# GlacTracker_PSU.net
KiCad netlist of a schematic drawn in EAGLE
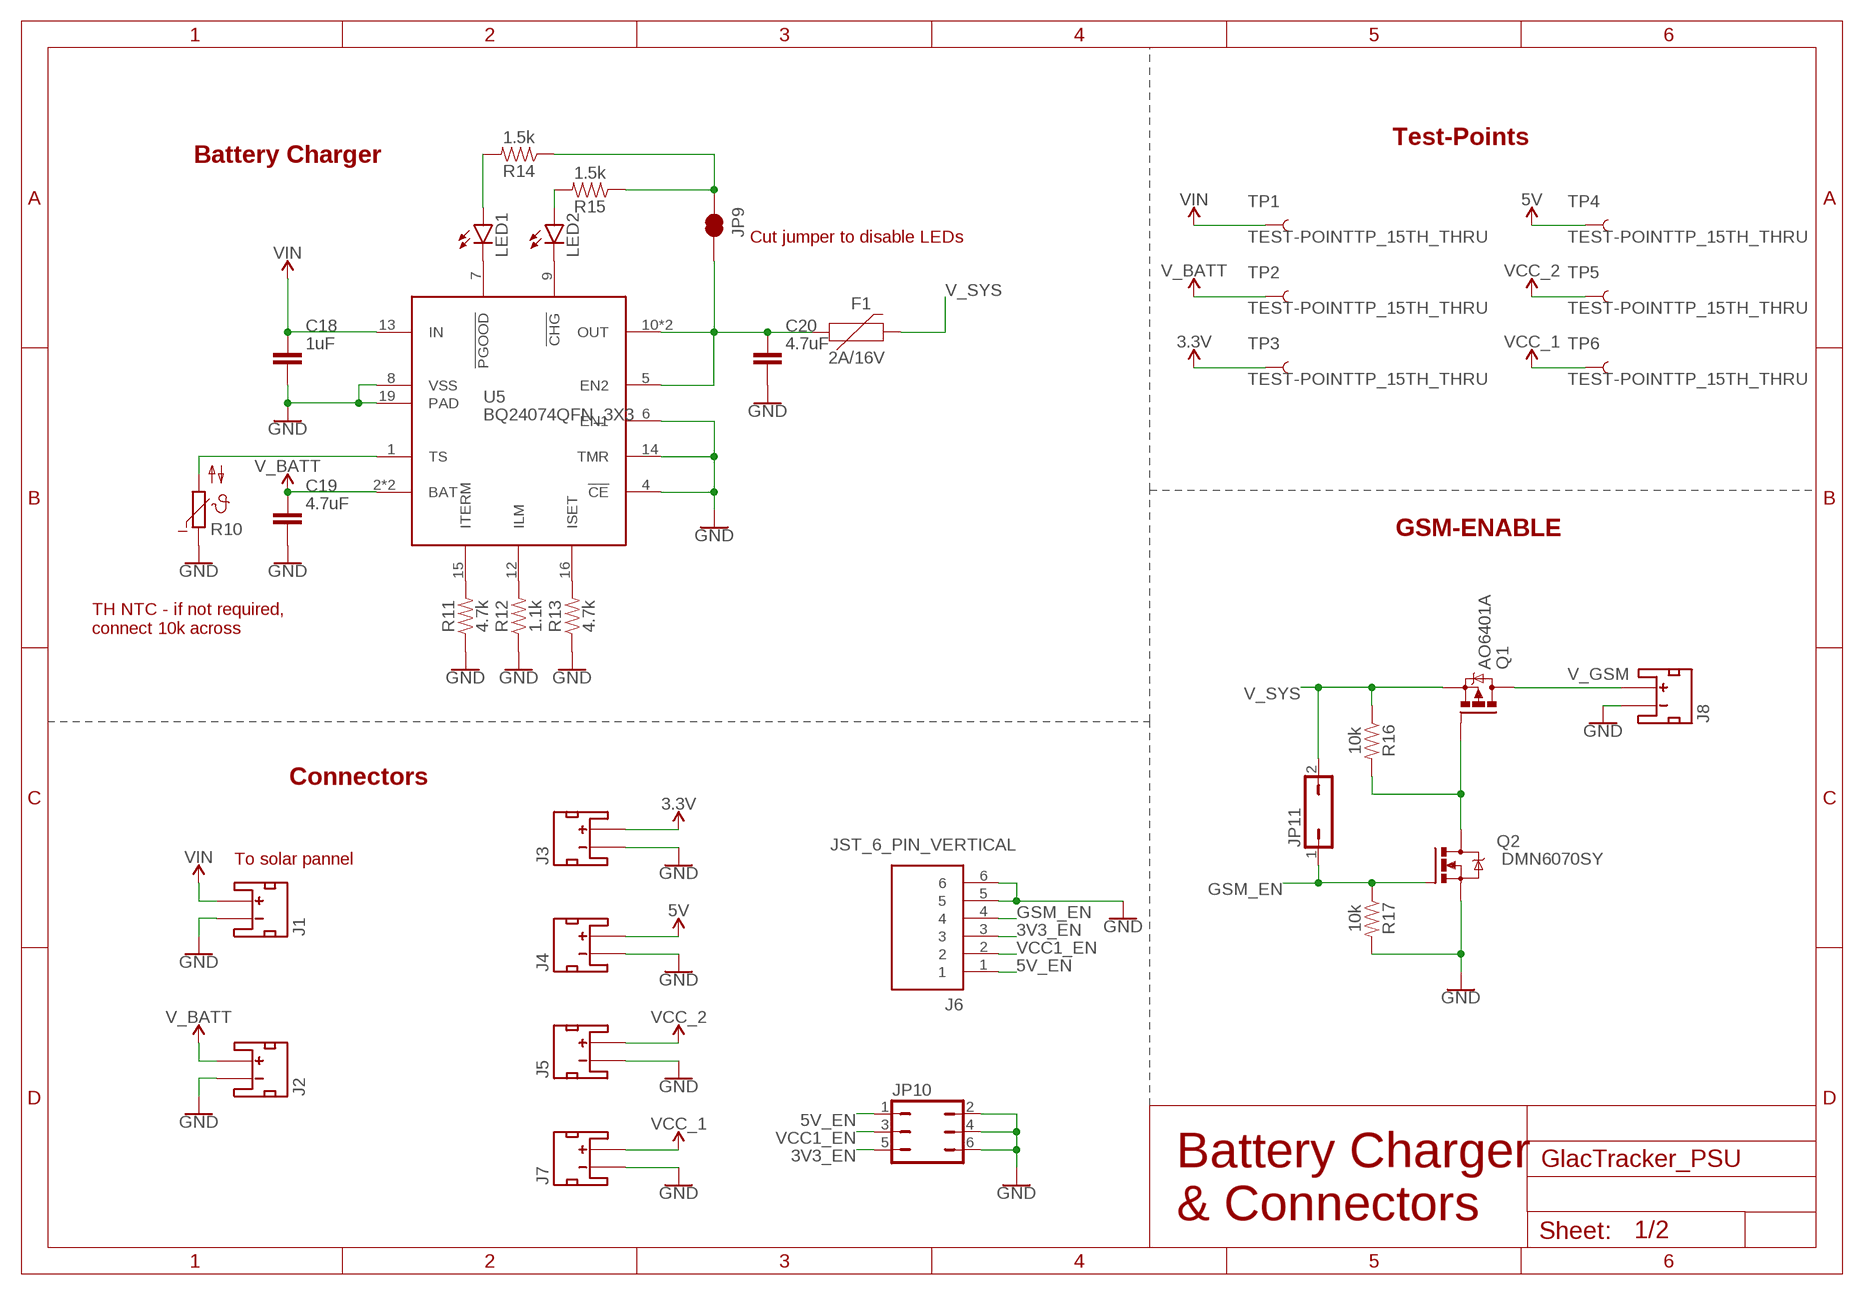
[diagram p0: schematic, sheet 1]
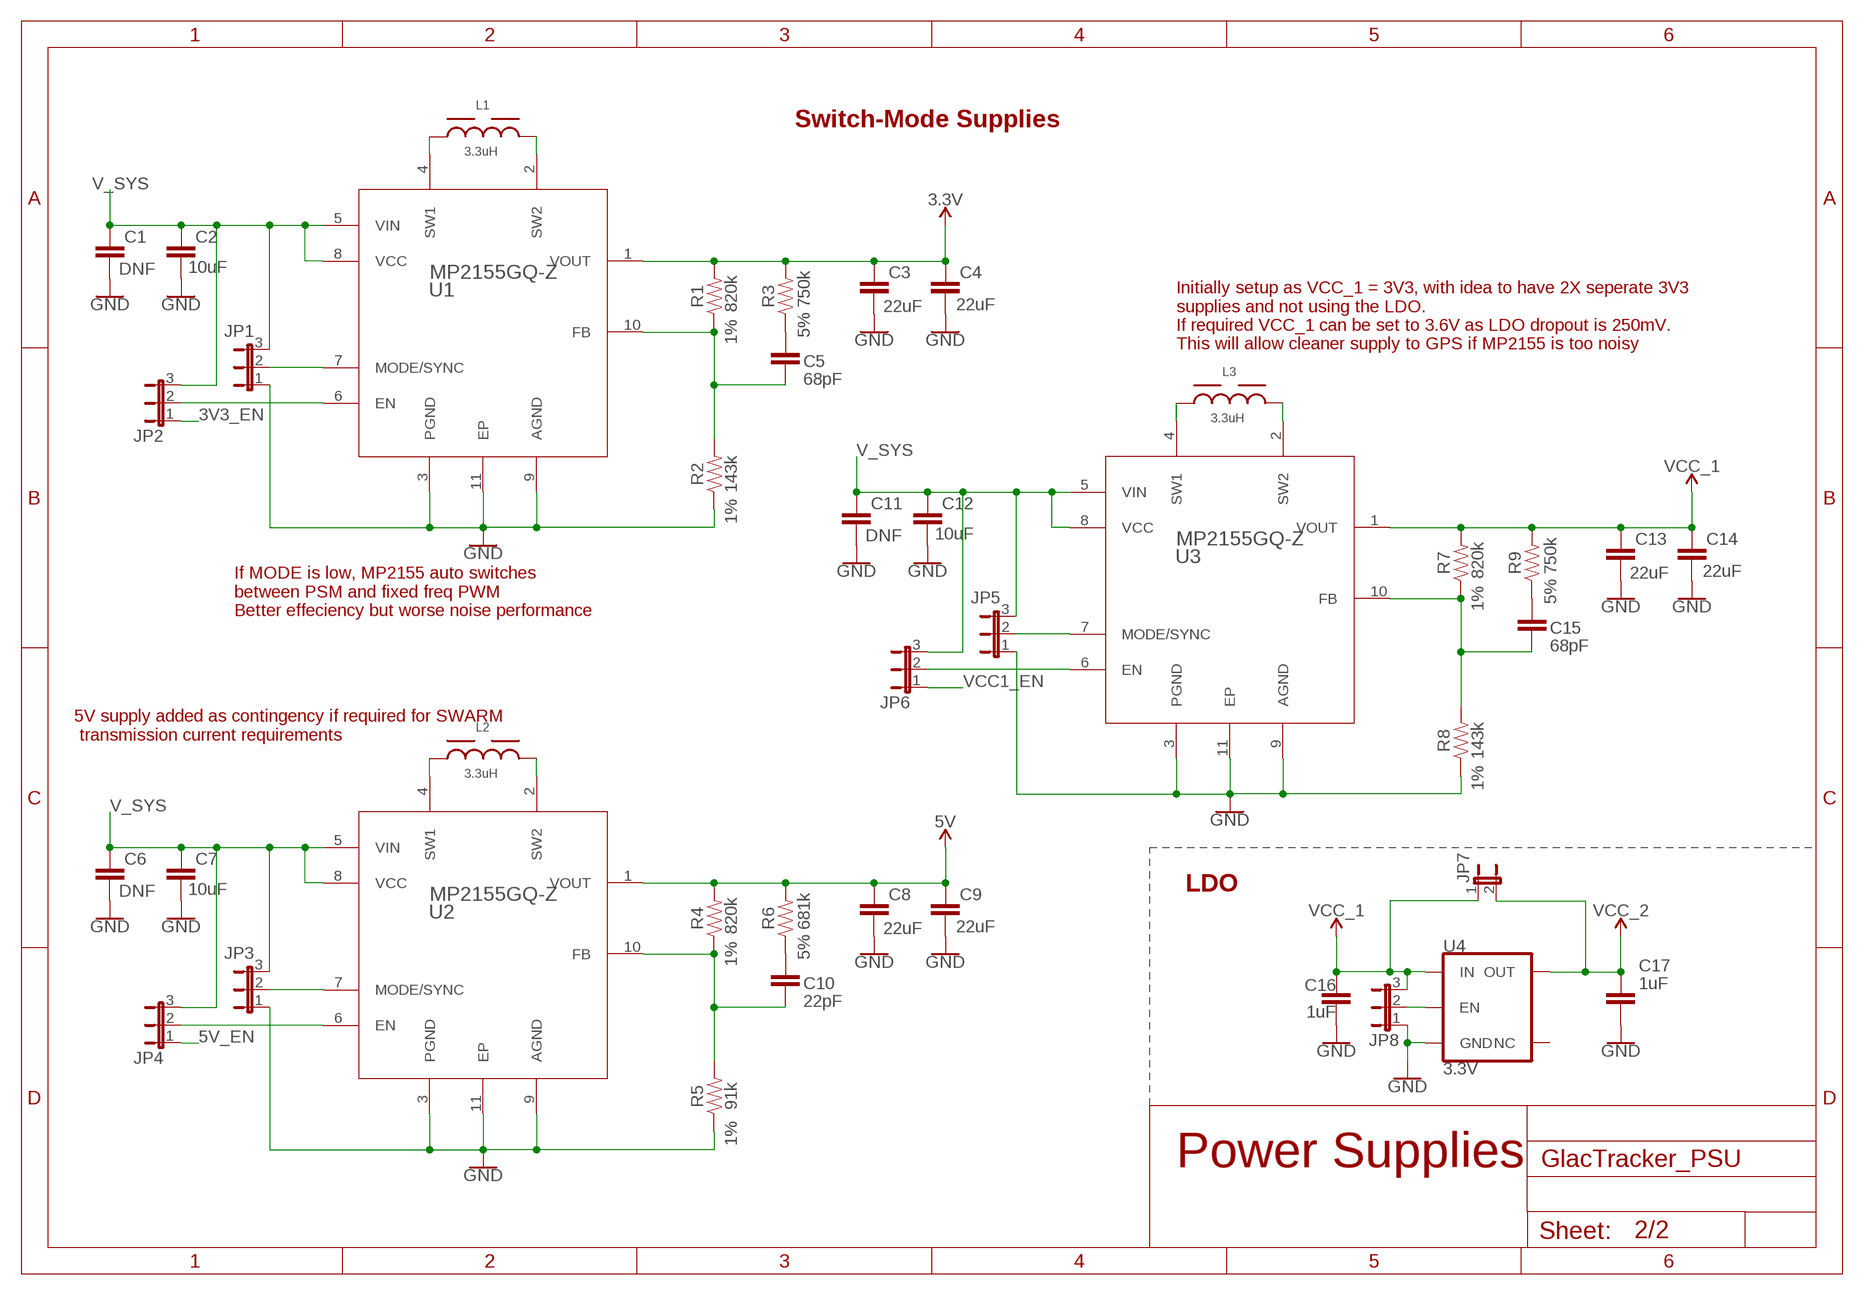
[diagram p1: schematic, sheet 2]

(export (version "E")
  (design (tool "Eeschema 10.0.6"))
  (components
    (comp (ref "C1")
      (value "DNF")
      (footprint "eagle-import:CAPC2012X110")
      (libsource (lib "eagle-import") (part "CCHIP-0805(2012-METRIC)_"))
    )
    (comp (ref "C2")
      (value "10uF")
      (footprint "eagle-import:CAPC2012X110")
      (fields (field (name "TYPE") "X7R") (field (name "VOLTAGE_RATING") "6.3V"))
      (libsource (lib "eagle-import") (part "CCHIP-0805(2012-METRIC)_"))
    )
    (comp (ref "C3")
      (value "22uF")
      (footprint "eagle-import:CAPC2012X110")
      (fields (field (name "TYPE") "X5R") (field (name "VOLTAGE_RATING") "10V"))
      (libsource (lib "eagle-import") (part "CCHIP-0805(2012-METRIC)_"))
    )
    (comp (ref "C4")
      (value "22uF")
      (footprint "eagle-import:CAPC2012X110")
      (fields (field (name "TYPE") "X5R") (field (name "VOLTAGE_RATING") "10V"))
      (libsource (lib "eagle-import") (part "CCHIP-0805(2012-METRIC)_"))
    )
    (comp (ref "C5")
      (value "68pF")
      (footprint "eagle-import:CAPC1608X85")
      (fields (field (name "TYPE") "X7R") (field (name "VOLTAGE_RATING") "50V"))
      (libsource (lib "eagle-import") (part "CCHIP-0603(1608-METRIC)_"))
    )
    (comp (ref "C6")
      (value "DNF")
      (footprint "eagle-import:CAPC2012X110")
      (libsource (lib "eagle-import") (part "CCHIP-0805(2012-METRIC)_"))
    )
    (comp (ref "C7")
      (value "10uF")
      (footprint "eagle-import:CAPC2012X110")
      (fields (field (name "TYPE") "X7R") (field (name "VOLTAGE_RATING") "6.3V"))
      (libsource (lib "eagle-import") (part "CCHIP-0805(2012-METRIC)_"))
    )
    (comp (ref "C8")
      (value "22uF")
      (footprint "eagle-import:CAPC2012X110")
      (fields (field (name "TYPE") "X5R") (field (name "VOLTAGE_RATING") "10V"))
      (libsource (lib "eagle-import") (part "CCHIP-0805(2012-METRIC)_"))
    )
    (comp (ref "C9")
      (value "22uF")
      (footprint "eagle-import:CAPC2012X110")
      (fields (field (name "TYPE") "X5R") (field (name "VOLTAGE_RATING") "10V"))
      (libsource (lib "eagle-import") (part "CCHIP-0805(2012-METRIC)_"))
    )
    (comp (ref "C10")
      (value "22pF")
      (footprint "eagle-import:CAPC1608X85")
      (fields (field (name "TYPE") "X7R") (field (name "VOLTAGE_RATING") "50V"))
      (libsource (lib "eagle-import") (part "CCHIP-0603(1608-METRIC)_"))
    )
    (comp (ref "C11")
      (value "DNF")
      (footprint "eagle-import:CAPC2012X110")
      (libsource (lib "eagle-import") (part "CCHIP-0805(2012-METRIC)_"))
    )
    (comp (ref "C12")
      (value "10uF")
      (footprint "eagle-import:CAPC2012X110")
      (fields (field (name "TYPE") "X7R") (field (name "VOLTAGE_RATING") "6.3V"))
      (libsource (lib "eagle-import") (part "CCHIP-0805(2012-METRIC)_"))
    )
    (comp (ref "C13")
      (value "22uF")
      (footprint "eagle-import:CAPC2012X110")
      (fields (field (name "TYPE") "X5R") (field (name "VOLTAGE_RATING") "10V"))
      (libsource (lib "eagle-import") (part "CCHIP-0805(2012-METRIC)_"))
    )
    (comp (ref "C14")
      (value "22uF")
      (footprint "eagle-import:CAPC2012X110")
      (fields (field (name "TYPE") "X5R") (field (name "VOLTAGE_RATING") "10V"))
      (libsource (lib "eagle-import") (part "CCHIP-0805(2012-METRIC)_"))
    )
    (comp (ref "C15")
      (value "68pF")
      (footprint "eagle-import:CAPC1608X85")
      (fields (field (name "TYPE") "X7R") (field (name "VOLTAGE_RATING") "50V"))
      (libsource (lib "eagle-import") (part "CCHIP-0603(1608-METRIC)_"))
    )
    (comp (ref "C16")
      (value "1uF")
      (footprint "eagle-import:CAPC2012X110")
      (libsource (lib "eagle-import") (part "CCHIP-0805(2012-METRIC)_"))
    )
    (comp (ref "C17")
      (value "1uF")
      (footprint "eagle-import:CAPC2012X110")
      (libsource (lib "eagle-import") (part "CCHIP-0805(2012-METRIC)_"))
    )
    (comp (ref "JP1")
      (value "JP2E")
      (footprint "eagle-import:JP2")
      (libsource (lib "eagle-import") (part "JP2E"))
    )
    (comp (ref "JP2")
      (value "JP2E")
      (footprint "eagle-import:JP2")
      (libsource (lib "eagle-import") (part "JP2E"))
    )
    (comp (ref "JP3")
      (value "JP2E")
      (footprint "eagle-import:JP2")
      (libsource (lib "eagle-import") (part "JP2E"))
    )
    (comp (ref "JP4")
      (value "JP2E")
      (footprint "eagle-import:JP2")
      (libsource (lib "eagle-import") (part "JP2E"))
    )
    (comp (ref "JP5")
      (value "JP2E")
      (footprint "eagle-import:JP2")
      (libsource (lib "eagle-import") (part "JP2E"))
    )
    (comp (ref "JP6")
      (value "JP2E")
      (footprint "eagle-import:JP2")
      (libsource (lib "eagle-import") (part "JP2E"))
    )
    (comp (ref "JP7")
      (value "JP1E")
      (footprint "eagle-import:JP1")
      (libsource (lib "eagle-import") (part "JP1E"))
    )
    (comp (ref "JP8")
      (value "JP2E")
      (footprint "eagle-import:JP2")
      (libsource (lib "eagle-import") (part "JP2E"))
    )
    (comp (ref "L1")
      (value "3.3uH")
      (footprint "eagle-import:WE-HCI_7050")
      (libsource (lib "eagle-import") (part "WE-HCI_7050_744314330"))
    )
    (comp (ref "L2")
      (value "3.3uH")
      (footprint "eagle-import:WE-HCI_7050")
      (libsource (lib "eagle-import") (part "WE-HCI_7050_744314330"))
    )
    (comp (ref "L3")
      (value "3.3uH")
      (footprint "eagle-import:WE-HCI_7050")
      (libsource (lib "eagle-import") (part "WE-HCI_7050_744314330"))
    )
    (comp (ref "R1")
      (value "820k")
      (footprint "eagle-import:0603")
      (fields (field (name "TOLERANCE") "1%"))
      (libsource (lib "eagle-import") (part "RESISTOR0603"))
    )
    (comp (ref "R2")
      (value "143k")
      (footprint "eagle-import:0603")
      (fields (field (name "TOLERANCE") "1%"))
      (libsource (lib "eagle-import") (part "RESISTOR0603"))
    )
    (comp (ref "R3")
      (value "750k")
      (footprint "eagle-import:0603")
      (fields (field (name "TOLERANCE") "5%"))
      (libsource (lib "eagle-import") (part "RESISTOR0603"))
    )
    (comp (ref "R4")
      (value "820k")
      (footprint "eagle-import:0603")
      (fields (field (name "TOLERANCE") "1%"))
      (libsource (lib "eagle-import") (part "RESISTOR0603"))
    )
    (comp (ref "R5")
      (value "91k")
      (footprint "eagle-import:0603")
      (fields (field (name "TOLERANCE") "1%"))
      (libsource (lib "eagle-import") (part "RESISTOR0603"))
    )
    (comp (ref "R6")
      (value "681k")
      (footprint "eagle-import:0603")
      (fields (field (name "TOLERANCE") "5%"))
      (libsource (lib "eagle-import") (part "RESISTOR0603"))
    )
    (comp (ref "R7")
      (value "820k")
      (footprint "eagle-import:0603")
      (fields (field (name "TOLERANCE") "1%"))
      (libsource (lib "eagle-import") (part "RESISTOR0603"))
    )
    (comp (ref "R8")
      (value "143k")
      (footprint "eagle-import:0603")
      (fields (field (name "TOLERANCE") "1%"))
      (libsource (lib "eagle-import") (part "RESISTOR0603"))
    )
    (comp (ref "R9")
      (value "750k")
      (footprint "eagle-import:0603")
      (fields (field (name "TOLERANCE") "5%"))
      (libsource (lib "eagle-import") (part "RESISTOR0603"))
    )
    (comp (ref "U1")
      (value "MP2155GQ-Z")
      (footprint "eagle-import:QFN-10_MP2155_MNP")
      (fields (field (name "COPYRIGHT") "Copyright (C) 2022 Ultra Librarian. All rights reserved."))
      (libsource (lib "eagle-import") (part "MP2155GQ-Z"))
    )
    (comp (ref "U2")
      (value "MP2155GQ-Z")
      (footprint "eagle-import:QFN-10_MP2155_MNP")
      (fields (field (name "COPYRIGHT") "Copyright (C) 2022 Ultra Librarian. All rights reserved."))
      (libsource (lib "eagle-import") (part "MP2155GQ-Z"))
    )
    (comp (ref "U3")
      (value "MP2155GQ-Z")
      (footprint "eagle-import:QFN-10_MP2155_MNP")
      (fields (field (name "COPYRIGHT") "Copyright (C) 2022 Ultra Librarian. All rights reserved."))
      (libsource (lib "eagle-import") (part "MP2155GQ-Z"))
    )
    (comp (ref "U4")
      (value "3.3V")
      (footprint "eagle-import:SOT23-5")
      (libsource (lib "eagle-import") (part "V_REG_AP2112K-3.3V"))
    )
    (comp (ref "C18")
      (value "1uF")
      (footprint "eagle-import:CAPC2012X110")
      (libsource (lib "eagle-import") (part "CCHIP-0805(2012-METRIC)_"))
    )
    (comp (ref "C19")
      (value "4.7uF")
      (footprint "eagle-import:CAPC2012X110")
      (libsource (lib "eagle-import") (part "CCHIP-0805(2012-METRIC)_"))
    )
    (comp (ref "C20")
      (value "4.7uF")
      (footprint "eagle-import:CAPC2012X110")
      (libsource (lib "eagle-import") (part "CCHIP-0805(2012-METRIC)_"))
    )
    (comp (ref "F1")
      (value "2A/16V")
      (footprint "eagle-import:F1812")
      (libsource (lib "eagle-import") (part "PPTC_2A"))
    )
    (comp (ref "J1")
      (value "JST_2MM_MALE")
      (footprint "eagle-import:JST-2-SMD")
      (libsource (lib "eagle-import") (part "JST_2MM_MALE"))
    )
    (comp (ref "J2")
      (value "JST_2MM_MALE")
      (footprint "eagle-import:JST-2-SMD")
      (libsource (lib "eagle-import") (part "JST_2MM_MALE"))
    )
    (comp (ref "J3")
      (value "JST_2MM_MALE")
      (footprint "eagle-import:JST-2-SMD")
      (libsource (lib "eagle-import") (part "JST_2MM_MALE"))
    )
    (comp (ref "J4")
      (value "JST_2MM_MALE")
      (footprint "eagle-import:JST-2-SMD")
      (libsource (lib "eagle-import") (part "JST_2MM_MALE"))
    )
    (comp (ref "J5")
      (value "JST_2MM_MALE")
      (footprint "eagle-import:JST-2-SMD")
      (libsource (lib "eagle-import") (part "JST_2MM_MALE"))
    )
    (comp (ref "J6")
      (value "JST_6_PIN_VERTICAL")
      (footprint "eagle-import:JST-6-SMD-VERT-1.0MM")
      (libsource (lib "eagle-import") (part "JST_6_PIN_VERTICAL"))
    )
    (comp (ref "J7")
      (value "JST_2MM_MALE")
      (footprint "eagle-import:JST-2-SMD")
      (libsource (lib "eagle-import") (part "JST_2MM_MALE"))
    )
    (comp (ref "J8")
      (value "JST_2MM_MALE")
      (footprint "eagle-import:JST-2-SMD")
      (libsource (lib "eagle-import") (part "JST_2MM_MALE"))
    )
    (comp (ref "JP9")
      (value "JUMPER-SMT_2_NC_TRACE_SILK")
      (footprint "eagle-import:SMT-JUMPER_2_NC_TRACE_SILK")
      (libsource (lib "eagle-import") (part "JUMPER-SMT_2_NC_TRACE_SILK"))
    )
    (comp (ref "JP10")
      (value "JP3Q")
      (footprint "eagle-import:JP3Q")
      (libsource (lib "eagle-import") (part "JP3Q"))
    )
    (comp (ref "JP11")
      (value "JP1Q")
      (footprint "eagle-import:JP1")
      (libsource (lib "eagle-import") (part "JP1Q"))
    )
    (comp (ref "LED1")
      (value "LEDSML0805")
      (footprint "eagle-import:SML0805")
      (libsource (lib "eagle-import") (part "LEDSML0805"))
    )
    (comp (ref "LED2")
      (value "LEDSML0805")
      (footprint "eagle-import:SML0805")
      (libsource (lib "eagle-import") (part "LEDSML0805"))
    )
    (comp (ref "Q1")
      (value "AO6401A")
      (footprint "eagle-import:TSOP-6")
      (libsource (lib "eagle-import") (part "AO6401A"))
    )
    (comp (ref "Q2")
      (value "DMN6070SY")
      (footprint "eagle-import:SOT-89-3")
      (libsource (lib "eagle-import") (part "DMN6070SY-13"))
    )
    (comp (ref "R10")
      (value "DNF")
      (footprint "eagle-import:P640")
      (libsource (lib "eagle-import") (part "NTC640"))
    )
    (comp (ref "R11")
      (value "4.7k")
      (footprint "eagle-import:0603")
      (libsource (lib "eagle-import") (part "RESISTOR0603"))
    )
    (comp (ref "R12")
      (value "1.1k")
      (footprint "eagle-import:0603")
      (libsource (lib "eagle-import") (part "RESISTOR0603"))
    )
    (comp (ref "R13")
      (value "4.7k")
      (footprint "eagle-import:0603")
      (libsource (lib "eagle-import") (part "RESISTOR0603"))
    )
    (comp (ref "R14")
      (value "1.5k")
      (footprint "eagle-import:0603")
      (libsource (lib "eagle-import") (part "RESISTOR0603"))
    )
    (comp (ref "R15")
      (value "1.5k")
      (footprint "eagle-import:0603")
      (libsource (lib "eagle-import") (part "RESISTOR0603"))
    )
    (comp (ref "R16")
      (value "10k")
      (footprint "eagle-import:0603")
      (libsource (lib "eagle-import") (part "RESISTOR0603"))
    )
    (comp (ref "R17")
      (value "10k")
      (footprint "eagle-import:0603")
      (libsource (lib "eagle-import") (part "RESISTOR0603"))
    )
    (comp (ref "TP1")
      (value "TEST-POINTTP_15TH_THRU")
      (footprint "eagle-import:TP_15TH")
      (libsource (lib "eagle-import") (part "TEST-POINTTP_15TH_THRU"))
    )
    (comp (ref "TP2")
      (value "TEST-POINTTP_15TH_THRU")
      (footprint "eagle-import:TP_15TH")
      (libsource (lib "eagle-import") (part "TEST-POINTTP_15TH_THRU"))
    )
    (comp (ref "TP3")
      (value "TEST-POINTTP_15TH_THRU")
      (footprint "eagle-import:TP_15TH")
      (libsource (lib "eagle-import") (part "TEST-POINTTP_15TH_THRU"))
    )
    (comp (ref "TP4")
      (value "TEST-POINTTP_15TH_THRU")
      (footprint "eagle-import:TP_15TH")
      (libsource (lib "eagle-import") (part "TEST-POINTTP_15TH_THRU"))
    )
    (comp (ref "TP5")
      (value "TEST-POINTTP_15TH_THRU")
      (footprint "eagle-import:TP_15TH")
      (libsource (lib "eagle-import") (part "TEST-POINTTP_15TH_THRU"))
    )
    (comp (ref "TP6")
      (value "TEST-POINTTP_15TH_THRU")
      (footprint "eagle-import:TP_15TH")
      (libsource (lib "eagle-import") (part "TEST-POINTTP_15TH_THRU"))
    )
    (comp (ref "U5")
      (value "BQ24074QFN_3X3")
      (footprint "eagle-import:QFN_3X3")
      (libsource (lib "eagle-import") (part "BQ24074QFN_3X3"))
    )
  )
  (nets
    (net (code "1") (name "3.3V") (class "Default")
      (node (ref "C3") (pin "1") (pinfunction "1_1") (pintype "passive"))
      (node (ref "C4") (pin "1") (pinfunction "1_1") (pintype "passive"))
      (node (ref "J3") (pin "2") (pinfunction "+_2") (pintype "bidirectional"))
      (node (ref "R1") (pin "2") (pinfunction "2_2") (pintype "passive"))
      (node (ref "R3") (pin "2") (pinfunction "2_2") (pintype "passive"))
      (node (ref "TP3") (pin "P$1") (pinfunction "1_P$1") (pintype "bidirectional"))
      (node (ref "U1") (pin "1") (pinfunction "VOUT_1") (pintype "power_in"))
    )
    (net (code "2") (name "3V3_EN") (class "Default")
      (node (ref "J6") (pin "3") (pinfunction "3_3") (pintype "bidirectional"))
      (node (ref "JP10") (pin "5") (pinfunction "5_5") (pintype "passive"))
      (node (ref "JP2") (pin "1") (pinfunction "1_1") (pintype "passive"))
    )
    (net (code "3") (name "5V") (class "Default")
      (node (ref "C8") (pin "1") (pinfunction "1_1") (pintype "passive"))
      (node (ref "C9") (pin "1") (pinfunction "1_1") (pintype "passive"))
      (node (ref "J4") (pin "2") (pinfunction "+_2") (pintype "bidirectional"))
      (node (ref "R4") (pin "2") (pinfunction "2_2") (pintype "passive"))
      (node (ref "R6") (pin "2") (pinfunction "2_2") (pintype "passive"))
      (node (ref "TP4") (pin "P$1") (pinfunction "1_P$1") (pintype "bidirectional"))
      (node (ref "U2") (pin "1") (pinfunction "VOUT_1") (pintype "power_in"))
    )
    (net (code "4") (name "5V_EN") (class "Default")
      (node (ref "J6") (pin "1") (pinfunction "1_1") (pintype "bidirectional"))
      (node (ref "JP10") (pin "1") (pinfunction "1_1") (pintype "passive"))
      (node (ref "JP4") (pin "1") (pinfunction "1_1") (pintype "passive"))
    )
    (net (code "5") (name "GND") (class "Default")
      (node (ref "C1") (pin "2") (pinfunction "2_2") (pintype "passive"))
      (node (ref "C11") (pin "2") (pinfunction "2_2") (pintype "passive"))
      (node (ref "C12") (pin "2") (pinfunction "2_2") (pintype "passive"))
      (node (ref "C13") (pin "2") (pinfunction "2_2") (pintype "passive"))
      (node (ref "C14") (pin "2") (pinfunction "2_2") (pintype "passive"))
      (node (ref "C16") (pin "2") (pinfunction "2_2") (pintype "passive"))
      (node (ref "C17") (pin "2") (pinfunction "2_2") (pintype "passive"))
      (node (ref "C18") (pin "2") (pinfunction "2_2") (pintype "passive"))
      (node (ref "C19") (pin "2") (pinfunction "2_2") (pintype "passive"))
      (node (ref "C2") (pin "2") (pinfunction "2_2") (pintype "passive"))
      (node (ref "C20") (pin "2") (pinfunction "2_2") (pintype "passive"))
      (node (ref "C3") (pin "2") (pinfunction "2_2") (pintype "passive"))
      (node (ref "C4") (pin "2") (pinfunction "2_2") (pintype "passive"))
      (node (ref "C6") (pin "2") (pinfunction "2_2") (pintype "passive"))
      (node (ref "C7") (pin "2") (pinfunction "2_2") (pintype "passive"))
      (node (ref "C8") (pin "2") (pinfunction "2_2") (pintype "passive"))
      (node (ref "C9") (pin "2") (pinfunction "2_2") (pintype "passive"))
      (node (ref "J1") (pin "1") (pinfunction "-_1") (pintype "bidirectional"))
      (node (ref "J2") (pin "1") (pinfunction "-_1") (pintype "bidirectional"))
      (node (ref "J3") (pin "1") (pinfunction "-_1") (pintype "bidirectional"))
      (node (ref "J4") (pin "1") (pinfunction "-_1") (pintype "bidirectional"))
      (node (ref "J5") (pin "1") (pinfunction "-_1") (pintype "bidirectional"))
      (node (ref "J6") (pin "5") (pinfunction "5_5") (pintype "bidirectional"))
      (node (ref "J6") (pin "6") (pinfunction "6_6") (pintype "bidirectional"))
      (node (ref "J7") (pin "1") (pinfunction "-_1") (pintype "bidirectional"))
      (node (ref "J8") (pin "1") (pinfunction "-_1") (pintype "bidirectional"))
      (node (ref "JP1") (pin "1") (pinfunction "1_1") (pintype "passive"))
      (node (ref "JP10") (pin "2") (pinfunction "2_2") (pintype "passive"))
      (node (ref "JP10") (pin "4") (pinfunction "4_4") (pintype "passive"))
      (node (ref "JP10") (pin "6") (pinfunction "6_6") (pintype "passive"))
      (node (ref "JP3") (pin "1") (pinfunction "1_1") (pintype "passive"))
      (node (ref "JP5") (pin "1") (pinfunction "1_1") (pintype "passive"))
      (node (ref "JP8") (pin "1") (pinfunction "1_1") (pintype "passive"))
      (node (ref "Q2") (pin "3") (pinfunction "S_3") (pintype "passive"))
      (node (ref "R10") (pin "1") (pinfunction "1_1") (pintype "passive"))
      (node (ref "R11") (pin "1") (pinfunction "1_1") (pintype "passive"))
      (node (ref "R12") (pin "1") (pinfunction "1_1") (pintype "passive"))
      (node (ref "R13") (pin "1") (pinfunction "1_1") (pintype "passive"))
      (node (ref "R17") (pin "2") (pinfunction "2_2") (pintype "passive"))
      (node (ref "R2") (pin "1") (pinfunction "1_1") (pintype "passive"))
      (node (ref "R5") (pin "1") (pinfunction "1_1") (pintype "passive"))
      (node (ref "R8") (pin "1") (pinfunction "1_1") (pintype "passive"))
      (node (ref "U1") (pin "11") (pinfunction "EP_11") (pintype "power_in"))
      (node (ref "U1") (pin "3") (pinfunction "PGND_3") (pintype "power_in"))
      (node (ref "U1") (pin "9") (pinfunction "AGND_9") (pintype "passive"))
      (node (ref "U2") (pin "11") (pinfunction "EP_11") (pintype "power_in"))
      (node (ref "U2") (pin "3") (pinfunction "PGND_3") (pintype "power_in"))
      (node (ref "U2") (pin "9") (pinfunction "AGND_9") (pintype "passive"))
      (node (ref "U3") (pin "11") (pinfunction "EP_11") (pintype "power_in"))
      (node (ref "U3") (pin "3") (pinfunction "PGND_3") (pintype "power_in"))
      (node (ref "U3") (pin "9") (pinfunction "AGND_9") (pintype "passive"))
      (node (ref "U4") (pin "2") (pinfunction "GND_2") (pintype "input"))
      (node (ref "U5") (pin "14") (pinfunction "TMR_14") (pintype "bidirectional"))
      (node (ref "U5") (pin "19") (pinfunction "PAD_19") (pintype "bidirectional"))
      (node (ref "U5") (pin "4") (pinfunction "~{CE}_4") (pintype "bidirectional"))
      (node (ref "U5") (pin "6") (pinfunction "EN1_6") (pintype "bidirectional"))
      (node (ref "U5") (pin "8") (pinfunction "VSS_8") (pintype "bidirectional"))
    )
    (net (code "6") (name "GSM_EN") (class "Default")
      (node (ref "J6") (pin "4") (pinfunction "4_4") (pintype "bidirectional"))
      (node (ref "JP11") (pin "1") (pinfunction "1_1") (pintype "passive"))
      (node (ref "Q2") (pin "1") (pinfunction "G_1") (pintype "passive"))
      (node (ref "R17") (pin "1") (pinfunction "1_1") (pintype "passive"))
    )
    (net (code "7") (name "Net-(C5-Pad1)") (class "Default")
      (node (ref "C5") (pin "1") (pinfunction "1_1") (pintype "passive"))
      (node (ref "R3") (pin "1") (pinfunction "1_1") (pintype "passive"))
    )
    (net (code "8") (name "Net-(C10-Pad1)") (class "Default")
      (node (ref "C10") (pin "1") (pinfunction "1_1") (pintype "passive"))
      (node (ref "R6") (pin "1") (pinfunction "1_1") (pintype "passive"))
    )
    (net (code "9") (name "Net-(C15-Pad1)") (class "Default")
      (node (ref "C15") (pin "1") (pinfunction "1_1") (pintype "passive"))
      (node (ref "R9") (pin "1") (pinfunction "1_1") (pintype "passive"))
    )
    (net (code "10") (name "Net-(JP9-Pad1)") (class "Default")
      (node (ref "JP9") (pin "1") (pinfunction "1_1") (pintype "passive"))
      (node (ref "R14") (pin "1") (pinfunction "1_1") (pintype "passive"))
      (node (ref "R15") (pin "1") (pinfunction "1_1") (pintype "passive"))
    )
    (net (code "11") (name "Net-(LED1-PadA)") (class "Default")
      (node (ref "LED1") (pin "A") (pinfunction "A_A") (pintype "passive"))
      (node (ref "R14") (pin "2") (pinfunction "2_2") (pintype "passive"))
    )
    (net (code "12") (name "Net-(LED2-PadA)") (class "Default")
      (node (ref "LED2") (pin "A") (pinfunction "A_A") (pintype "passive"))
      (node (ref "R15") (pin "2") (pinfunction "2_2") (pintype "passive"))
    )
    (net (code "13") (name "Net-(Q1-G)") (class "Default")
      (node (ref "Q1") (pin "3") (pinfunction "G_3") (pintype "passive"))
      (node (ref "Q2") (pin "2") (pinfunction "D_2") (pintype "passive"))
      (node (ref "Q2") (pin "4") (pinfunction "D_4") (pintype "passive"))
      (node (ref "R16") (pin "2") (pinfunction "2_2") (pintype "passive"))
    )
    (net (code "14") (name "Net-(U1-EN)") (class "Default")
      (node (ref "JP2") (pin "2") (pinfunction "2_2") (pintype "passive"))
      (node (ref "U1") (pin "6") (pinfunction "EN_6") (pintype "passive"))
    )
    (net (code "15") (name "Net-(U1-FB)") (class "Default")
      (node (ref "C5") (pin "2") (pinfunction "2_2") (pintype "passive"))
      (node (ref "R1") (pin "1") (pinfunction "1_1") (pintype "passive"))
      (node (ref "R2") (pin "2") (pinfunction "2_2") (pintype "passive"))
      (node (ref "U1") (pin "10") (pinfunction "FB_10") (pintype "passive"))
    )
    (net (code "16") (name "Net-(U1-MODE{slash}SYNC)") (class "Default")
      (node (ref "JP1") (pin "2") (pinfunction "2_2") (pintype "passive"))
      (node (ref "U1") (pin "7") (pinfunction "MODE/SYNC_7") (pintype "passive"))
    )
    (net (code "17") (name "Net-(U1-SW1)") (class "Default")
      (node (ref "L1") (pin "1") (pinfunction "1_1") (pintype "passive"))
      (node (ref "U1") (pin "4") (pinfunction "SW1_4") (pintype "passive"))
    )
    (net (code "18") (name "Net-(U1-SW2)") (class "Default")
      (node (ref "L1") (pin "2") (pinfunction "2_2") (pintype "passive"))
      (node (ref "U1") (pin "2") (pinfunction "SW2_2") (pintype "output"))
    )
    (net (code "19") (name "Net-(U2-EN)") (class "Default")
      (node (ref "JP4") (pin "2") (pinfunction "2_2") (pintype "passive"))
      (node (ref "U2") (pin "6") (pinfunction "EN_6") (pintype "passive"))
    )
    (net (code "20") (name "Net-(U2-FB)") (class "Default")
      (node (ref "C10") (pin "2") (pinfunction "2_2") (pintype "passive"))
      (node (ref "R4") (pin "1") (pinfunction "1_1") (pintype "passive"))
      (node (ref "R5") (pin "2") (pinfunction "2_2") (pintype "passive"))
      (node (ref "U2") (pin "10") (pinfunction "FB_10") (pintype "passive"))
    )
    (net (code "21") (name "Net-(U2-MODE{slash}SYNC)") (class "Default")
      (node (ref "JP3") (pin "2") (pinfunction "2_2") (pintype "passive"))
      (node (ref "U2") (pin "7") (pinfunction "MODE/SYNC_7") (pintype "passive"))
    )
    (net (code "22") (name "Net-(U2-SW1)") (class "Default")
      (node (ref "L2") (pin "1") (pinfunction "1_1") (pintype "passive"))
      (node (ref "U2") (pin "4") (pinfunction "SW1_4") (pintype "passive"))
    )
    (net (code "23") (name "Net-(U2-SW2)") (class "Default")
      (node (ref "L2") (pin "2") (pinfunction "2_2") (pintype "passive"))
      (node (ref "U2") (pin "2") (pinfunction "SW2_2") (pintype "output"))
    )
    (net (code "24") (name "Net-(U3-EN)") (class "Default")
      (node (ref "JP6") (pin "2") (pinfunction "2_2") (pintype "passive"))
      (node (ref "U3") (pin "6") (pinfunction "EN_6") (pintype "passive"))
    )
    (net (code "25") (name "Net-(U3-FB)") (class "Default")
      (node (ref "C15") (pin "2") (pinfunction "2_2") (pintype "passive"))
      (node (ref "R7") (pin "1") (pinfunction "1_1") (pintype "passive"))
      (node (ref "R8") (pin "2") (pinfunction "2_2") (pintype "passive"))
      (node (ref "U3") (pin "10") (pinfunction "FB_10") (pintype "passive"))
    )
    (net (code "26") (name "Net-(U3-MODE{slash}SYNC)") (class "Default")
      (node (ref "JP5") (pin "2") (pinfunction "2_2") (pintype "passive"))
      (node (ref "U3") (pin "7") (pinfunction "MODE/SYNC_7") (pintype "passive"))
    )
    (net (code "27") (name "Net-(U3-SW1)") (class "Default")
      (node (ref "L3") (pin "1") (pinfunction "1_1") (pintype "passive"))
      (node (ref "U3") (pin "4") (pinfunction "SW1_4") (pintype "passive"))
    )
    (net (code "28") (name "Net-(U3-SW2)") (class "Default")
      (node (ref "L3") (pin "2") (pinfunction "2_2") (pintype "passive"))
      (node (ref "U3") (pin "2") (pinfunction "SW2_2") (pintype "output"))
    )
    (net (code "29") (name "Net-(U4-EN)") (class "Default")
      (node (ref "JP8") (pin "2") (pinfunction "2_2") (pintype "passive"))
      (node (ref "U4") (pin "3") (pinfunction "EN_3") (pintype "input"))
    )
    (net (code "30") (name "Net-(U5-EN2)") (class "Default")
      (node (ref "C20") (pin "1") (pinfunction "1_1") (pintype "passive"))
      (node (ref "F1") (pin "1") (pinfunction "1_1") (pintype "bidirectional"))
      (node (ref "JP9") (pin "2") (pinfunction "2_2") (pintype "passive"))
      (node (ref "U5") (pin "10") (pinfunction "OUT_10") (pintype "bidirectional"))
      (node (ref "U5") (pin "11") (pinfunction "OUT_11") (pintype "bidirectional"))
      (node (ref "U5") (pin "5") (pinfunction "EN2_5") (pintype "bidirectional"))
    )
    (net (code "31") (name "Net-(U5-ILM)") (class "Default")
      (node (ref "R12") (pin "2") (pinfunction "2_2") (pintype "passive"))
      (node (ref "U5") (pin "12") (pinfunction "ILM_12") (pintype "bidirectional"))
    )
    (net (code "32") (name "Net-(U5-ISET)") (class "Default")
      (node (ref "R13") (pin "2") (pinfunction "2_2") (pintype "passive"))
      (node (ref "U5") (pin "16") (pinfunction "ISET_16") (pintype "bidirectional"))
    )
    (net (code "33") (name "Net-(U5-ITERM)") (class "Default")
      (node (ref "R11") (pin "2") (pinfunction "2_2") (pintype "passive"))
      (node (ref "U5") (pin "15") (pinfunction "ITERM_15") (pintype "bidirectional"))
    )
    (net (code "34") (name "Net-(U5-TS)") (class "Default")
      (node (ref "R10") (pin "2") (pinfunction "2_2") (pintype "passive"))
      (node (ref "U5") (pin "1") (pinfunction "TS_1") (pintype "bidirectional"))
    )
    (net (code "35") (name "Net-(U5-~{CHG})") (class "Default")
      (node (ref "LED2") (pin "C") (pinfunction "C_C") (pintype "passive"))
      (node (ref "U5") (pin "9") (pinfunction "~{CHG}_9") (pintype "bidirectional"))
    )
    (net (code "36") (name "Net-(U5-~{PGOOD})") (class "Default")
      (node (ref "LED1") (pin "C") (pinfunction "C_C") (pintype "passive"))
      (node (ref "U5") (pin "7") (pinfunction "~{PGOOD}_7") (pintype "bidirectional"))
    )
    (net (code "37") (name "VCC1_EN") (class "Default")
      (node (ref "J6") (pin "2") (pinfunction "2_2") (pintype "bidirectional"))
      (node (ref "JP10") (pin "3") (pinfunction "3_3") (pintype "passive"))
      (node (ref "JP6") (pin "1") (pinfunction "1_1") (pintype "passive"))
    )
    (net (code "38") (name "VCC_1") (class "Default")
      (node (ref "C13") (pin "1") (pinfunction "1_1") (pintype "passive"))
      (node (ref "C14") (pin "1") (pinfunction "1_1") (pintype "passive"))
      (node (ref "C16") (pin "1") (pinfunction "1_1") (pintype "passive"))
      (node (ref "J7") (pin "2") (pinfunction "+_2") (pintype "bidirectional"))
      (node (ref "JP7") (pin "1") (pinfunction "1_1") (pintype "passive"))
      (node (ref "JP8") (pin "3") (pinfunction "3_3") (pintype "passive"))
      (node (ref "R7") (pin "2") (pinfunction "2_2") (pintype "passive"))
      (node (ref "R9") (pin "2") (pinfunction "2_2") (pintype "passive"))
      (node (ref "TP6") (pin "P$1") (pinfunction "1_P$1") (pintype "bidirectional"))
      (node (ref "U3") (pin "1") (pinfunction "VOUT_1") (pintype "power_in"))
      (node (ref "U4") (pin "1") (pinfunction "IN_1") (pintype "input"))
    )
    (net (code "39") (name "VCC_2") (class "Default")
      (node (ref "C17") (pin "1") (pinfunction "1_1") (pintype "passive"))
      (node (ref "J5") (pin "2") (pinfunction "+_2") (pintype "bidirectional"))
      (node (ref "JP7") (pin "2") (pinfunction "2_2") (pintype "passive"))
      (node (ref "TP5") (pin "P$1") (pinfunction "1_P$1") (pintype "bidirectional"))
      (node (ref "U4") (pin "5") (pinfunction "OUT_5") (pintype "passive"))
    )
    (net (code "40") (name "VIN") (class "Default")
      (node (ref "C18") (pin "1") (pinfunction "1_1") (pintype "passive"))
      (node (ref "J1") (pin "2") (pinfunction "+_2") (pintype "bidirectional"))
      (node (ref "TP1") (pin "P$1") (pinfunction "1_P$1") (pintype "bidirectional"))
      (node (ref "U5") (pin "13") (pinfunction "IN_13") (pintype "bidirectional"))
    )
    (net (code "41") (name "V_BATT") (class "Default")
      (node (ref "C19") (pin "1") (pinfunction "1_1") (pintype "passive"))
      (node (ref "J2") (pin "2") (pinfunction "+_2") (pintype "bidirectional"))
      (node (ref "TP2") (pin "P$1") (pinfunction "1_P$1") (pintype "bidirectional"))
      (node (ref "U5") (pin "2") (pinfunction "BAT_2") (pintype "bidirectional"))
      (node (ref "U5") (pin "3") (pinfunction "BAT_3") (pintype "bidirectional"))
    )
    (net (code "42") (name "V_GSM") (class "Default")
      (node (ref "J8") (pin "2") (pinfunction "+_2") (pintype "bidirectional"))
      (node (ref "Q1") (pin "1") (pinfunction "D_1") (pintype "passive"))
      (node (ref "Q1") (pin "2") (pinfunction "D_2") (pintype "passive"))
      (node (ref "Q1") (pin "5") (pinfunction "D_5") (pintype "passive"))
      (node (ref "Q1") (pin "6") (pinfunction "D_6") (pintype "passive"))
    )
    (net (code "43") (name "V_SYS") (class "Default")
      (node (ref "C1") (pin "1") (pinfunction "1_1") (pintype "passive"))
      (node (ref "C11") (pin "1") (pinfunction "1_1") (pintype "passive"))
      (node (ref "C12") (pin "1") (pinfunction "1_1") (pintype "passive"))
      (node (ref "C2") (pin "1") (pinfunction "1_1") (pintype "passive"))
      (node (ref "C6") (pin "1") (pinfunction "1_1") (pintype "passive"))
      (node (ref "C7") (pin "1") (pinfunction "1_1") (pintype "passive"))
      (node (ref "F1") (pin "2") (pinfunction "2_2") (pintype "bidirectional"))
      (node (ref "JP1") (pin "3") (pinfunction "3_3") (pintype "passive"))
      (node (ref "JP11") (pin "2") (pinfunction "2_2") (pintype "passive"))
      (node (ref "JP2") (pin "3") (pinfunction "3_3") (pintype "passive"))
      (node (ref "JP3") (pin "3") (pinfunction "3_3") (pintype "passive"))
      (node (ref "JP4") (pin "3") (pinfunction "3_3") (pintype "passive"))
      (node (ref "JP5") (pin "3") (pinfunction "3_3") (pintype "passive"))
      (node (ref "JP6") (pin "3") (pinfunction "3_3") (pintype "passive"))
      (node (ref "Q1") (pin "4") (pinfunction "S_4") (pintype "passive"))
      (node (ref "R16") (pin "1") (pinfunction "1_1") (pintype "passive"))
      (node (ref "U1") (pin "5") (pinfunction "VIN_5") (pintype "power_in"))
      (node (ref "U1") (pin "8") (pinfunction "VCC_8") (pintype "power_in"))
      (node (ref "U2") (pin "5") (pinfunction "VIN_5") (pintype "power_in"))
      (node (ref "U2") (pin "8") (pinfunction "VCC_8") (pintype "power_in"))
      (node (ref "U3") (pin "5") (pinfunction "VIN_5") (pintype "power_in"))
      (node (ref "U3") (pin "8") (pinfunction "VCC_8") (pintype "power_in"))
    )
    (net (code "44") (name "unconnected-(J1-PAD1-PadNC1)") (class "Default")
      (node (ref "J1") (pin "NC1") (pinfunction "PAD1_NC1") (pintype "bidirectional"))
    )
    (net (code "45") (name "unconnected-(J1-PAD2-PadNC2)") (class "Default")
      (node (ref "J1") (pin "NC2") (pinfunction "PAD2_NC2") (pintype "bidirectional"))
    )
    (net (code "46") (name "unconnected-(J2-PAD1-PadNC1)") (class "Default")
      (node (ref "J2") (pin "NC1") (pinfunction "PAD1_NC1") (pintype "bidirectional"))
    )
    (net (code "47") (name "unconnected-(J2-PAD2-PadNC2)") (class "Default")
      (node (ref "J2") (pin "NC2") (pinfunction "PAD2_NC2") (pintype "bidirectional"))
    )
    (net (code "48") (name "unconnected-(J3-PAD1-PadNC1)") (class "Default")
      (node (ref "J3") (pin "NC1") (pinfunction "PAD1_NC1") (pintype "bidirectional"))
    )
    (net (code "49") (name "unconnected-(J3-PAD2-PadNC2)") (class "Default")
      (node (ref "J3") (pin "NC2") (pinfunction "PAD2_NC2") (pintype "bidirectional"))
    )
    (net (code "50") (name "unconnected-(J4-PAD1-PadNC1)") (class "Default")
      (node (ref "J4") (pin "NC1") (pinfunction "PAD1_NC1") (pintype "bidirectional"))
    )
    (net (code "51") (name "unconnected-(J4-PAD2-PadNC2)") (class "Default")
      (node (ref "J4") (pin "NC2") (pinfunction "PAD2_NC2") (pintype "bidirectional"))
    )
    (net (code "52") (name "unconnected-(J5-PAD1-PadNC1)") (class "Default")
      (node (ref "J5") (pin "NC1") (pinfunction "PAD1_NC1") (pintype "bidirectional"))
    )
    (net (code "53") (name "unconnected-(J5-PAD2-PadNC2)") (class "Default")
      (node (ref "J5") (pin "NC2") (pinfunction "PAD2_NC2") (pintype "bidirectional"))
    )
    (net (code "54") (name "unconnected-(J7-PAD1-PadNC1)") (class "Default")
      (node (ref "J7") (pin "NC1") (pinfunction "PAD1_NC1") (pintype "bidirectional"))
    )
    (net (code "55") (name "unconnected-(J7-PAD2-PadNC2)") (class "Default")
      (node (ref "J7") (pin "NC2") (pinfunction "PAD2_NC2") (pintype "bidirectional"))
    )
    (net (code "56") (name "unconnected-(J8-PAD1-PadNC1)") (class "Default")
      (node (ref "J8") (pin "NC1") (pinfunction "PAD1_NC1") (pintype "bidirectional"))
    )
    (net (code "57") (name "unconnected-(J8-PAD2-PadNC2)") (class "Default")
      (node (ref "J8") (pin "NC2") (pinfunction "PAD2_NC2") (pintype "bidirectional"))
    )
    (net (code "58") (name "unconnected-(U4-NC-Pad4)") (class "Default")
      (node (ref "U4") (pin "4") (pinfunction "NC_4") (pintype "no_connect"))
    )
  )
)
